# l293d_brkout.net
KiCad netlist of a schematic drawn in EAGLE
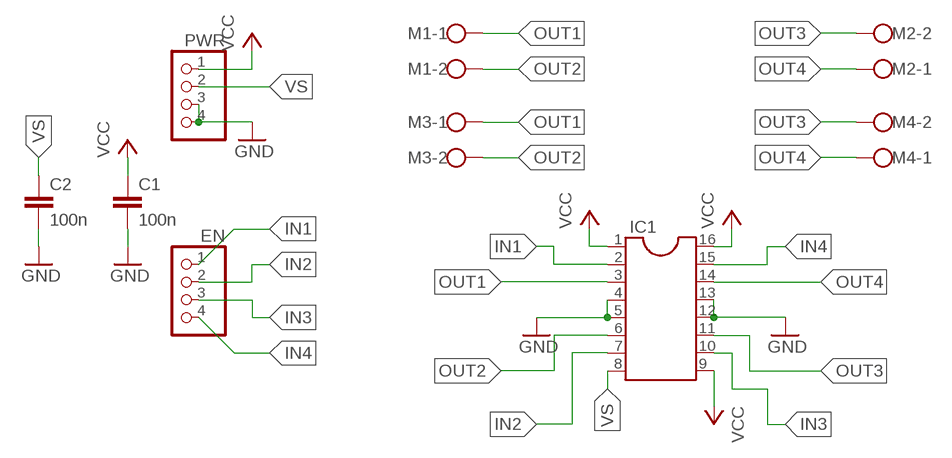
[diagram p0: schematic, sheet 1]

(export (version "E")
  (design (tool "Eeschema 10.0.6"))
  (components
    (comp (ref "C1")
      (value "100n")
      (footprint "eagle-import:C2.5-2")
      (libsource (lib "eagle-import") (part "C2.5/2"))
    )
    (comp (ref "C2")
      (value "100n")
      (footprint "eagle-import:C2.5-2")
      (libsource (lib "eagle-import") (part "C2.5/2"))
    )
    (comp (ref "EN")
      (value "PINHD-1X4")
      (footprint "eagle-import:1X04")
      (libsource (lib "eagle-import") (part "PINHD-1X4"))
    )
    (comp (ref "IC1")
      (value "DIL16S")
      (footprint "eagle-import:SOCKET-16")
      (libsource (lib "eagle-import") (part "DIL16S"))
    )
    (comp (ref "M1")
      (value "W237-102")
      (footprint "eagle-import:W237-102")
      (fields (field (name "MPN") "237-102"))
      (libsource (lib "eagle-import") (part "W237-102"))
    )
    (comp (ref "M2")
      (value "W237-102")
      (footprint "eagle-import:W237-102")
      (fields (field (name "MPN") "237-102"))
      (libsource (lib "eagle-import") (part "W237-102"))
    )
    (comp (ref "M3")
      (value "W237-102")
      (footprint "eagle-import:W237-102")
      (fields (field (name "MPN") "237-102"))
      (libsource (lib "eagle-import") (part "W237-102"))
    )
    (comp (ref "M4")
      (value "W237-102")
      (footprint "eagle-import:W237-102")
      (fields (field (name "MPN") "237-102"))
      (libsource (lib "eagle-import") (part "W237-102"))
    )
    (comp (ref "PWR")
      (value "PINHD-1X4")
      (footprint "eagle-import:1X04")
      (libsource (lib "eagle-import") (part "PINHD-1X4"))
    )
  )
  (nets
    (net (code "1") (name "GND") (class "Default")
      (node (ref "C1") (pin "2") (pinfunction "2_2") (pintype "passive"))
      (node (ref "C2") (pin "2") (pinfunction "2_2") (pintype "passive"))
      (node (ref "IC1") (pin "12") (pinfunction "12_12") (pintype "passive"))
      (node (ref "IC1") (pin "13") (pinfunction "13_13") (pintype "passive"))
      (node (ref "IC1") (pin "4") (pinfunction "4_4") (pintype "passive"))
      (node (ref "IC1") (pin "5") (pinfunction "5_5") (pintype "passive"))
      (node (ref "PWR") (pin "3") (pinfunction "3_3") (pintype "passive"))
      (node (ref "PWR") (pin "4") (pinfunction "4_4") (pintype "passive"))
    )
    (net (code "2") (name "IN1") (class "Default")
      (node (ref "EN") (pin "1") (pinfunction "1_1") (pintype "passive"))
      (node (ref "IC1") (pin "2") (pinfunction "2_2") (pintype "passive"))
    )
    (net (code "3") (name "IN2") (class "Default")
      (node (ref "EN") (pin "2") (pinfunction "2_2") (pintype "passive"))
      (node (ref "IC1") (pin "7") (pinfunction "7_7") (pintype "passive"))
    )
    (net (code "4") (name "IN3") (class "Default")
      (node (ref "EN") (pin "3") (pinfunction "3_3") (pintype "passive"))
      (node (ref "IC1") (pin "10") (pinfunction "10_10") (pintype "passive"))
    )
    (net (code "5") (name "IN4") (class "Default")
      (node (ref "EN") (pin "4") (pinfunction "4_4") (pintype "passive"))
      (node (ref "IC1") (pin "15") (pinfunction "15_15") (pintype "passive"))
    )
    (net (code "6") (name "OUT1") (class "Default")
      (node (ref "IC1") (pin "3") (pinfunction "3_3") (pintype "passive"))
      (node (ref "M1") (pin "1") (pinfunction "KL_1") (pintype "passive"))
      (node (ref "M3") (pin "1") (pinfunction "KL_1") (pintype "passive"))
    )
    (net (code "7") (name "OUT2") (class "Default")
      (node (ref "IC1") (pin "6") (pinfunction "6_6") (pintype "passive"))
      (node (ref "M1") (pin "2") (pinfunction "KL_2") (pintype "passive"))
      (node (ref "M3") (pin "2") (pinfunction "KL_2") (pintype "passive"))
    )
    (net (code "8") (name "OUT3") (class "Default")
      (node (ref "IC1") (pin "11") (pinfunction "11_11") (pintype "passive"))
      (node (ref "M2") (pin "2") (pinfunction "KL_2") (pintype "passive"))
      (node (ref "M4") (pin "2") (pinfunction "KL_2") (pintype "passive"))
    )
    (net (code "9") (name "OUT4") (class "Default")
      (node (ref "IC1") (pin "14") (pinfunction "14_14") (pintype "passive"))
      (node (ref "M2") (pin "1") (pinfunction "KL_1") (pintype "passive"))
      (node (ref "M4") (pin "1") (pinfunction "KL_1") (pintype "passive"))
    )
    (net (code "10") (name "VCC") (class "Default")
      (node (ref "C1") (pin "1") (pinfunction "1_1") (pintype "passive"))
      (node (ref "IC1") (pin "1") (pinfunction "1_1") (pintype "passive"))
      (node (ref "IC1") (pin "16") (pinfunction "16_16") (pintype "passive"))
      (node (ref "IC1") (pin "9") (pinfunction "9_9") (pintype "passive"))
      (node (ref "PWR") (pin "1") (pinfunction "1_1") (pintype "passive"))
    )
    (net (code "11") (name "VS") (class "Default")
      (node (ref "C2") (pin "1") (pinfunction "1_1") (pintype "passive"))
      (node (ref "IC1") (pin "8") (pinfunction "8_8") (pintype "passive"))
      (node (ref "PWR") (pin "2") (pinfunction "2_2") (pintype "passive"))
    )
  )
)
